# 05-AD9546_StrapsXtal.net
KiCad netlist of a schematic drawn in Altium Designer
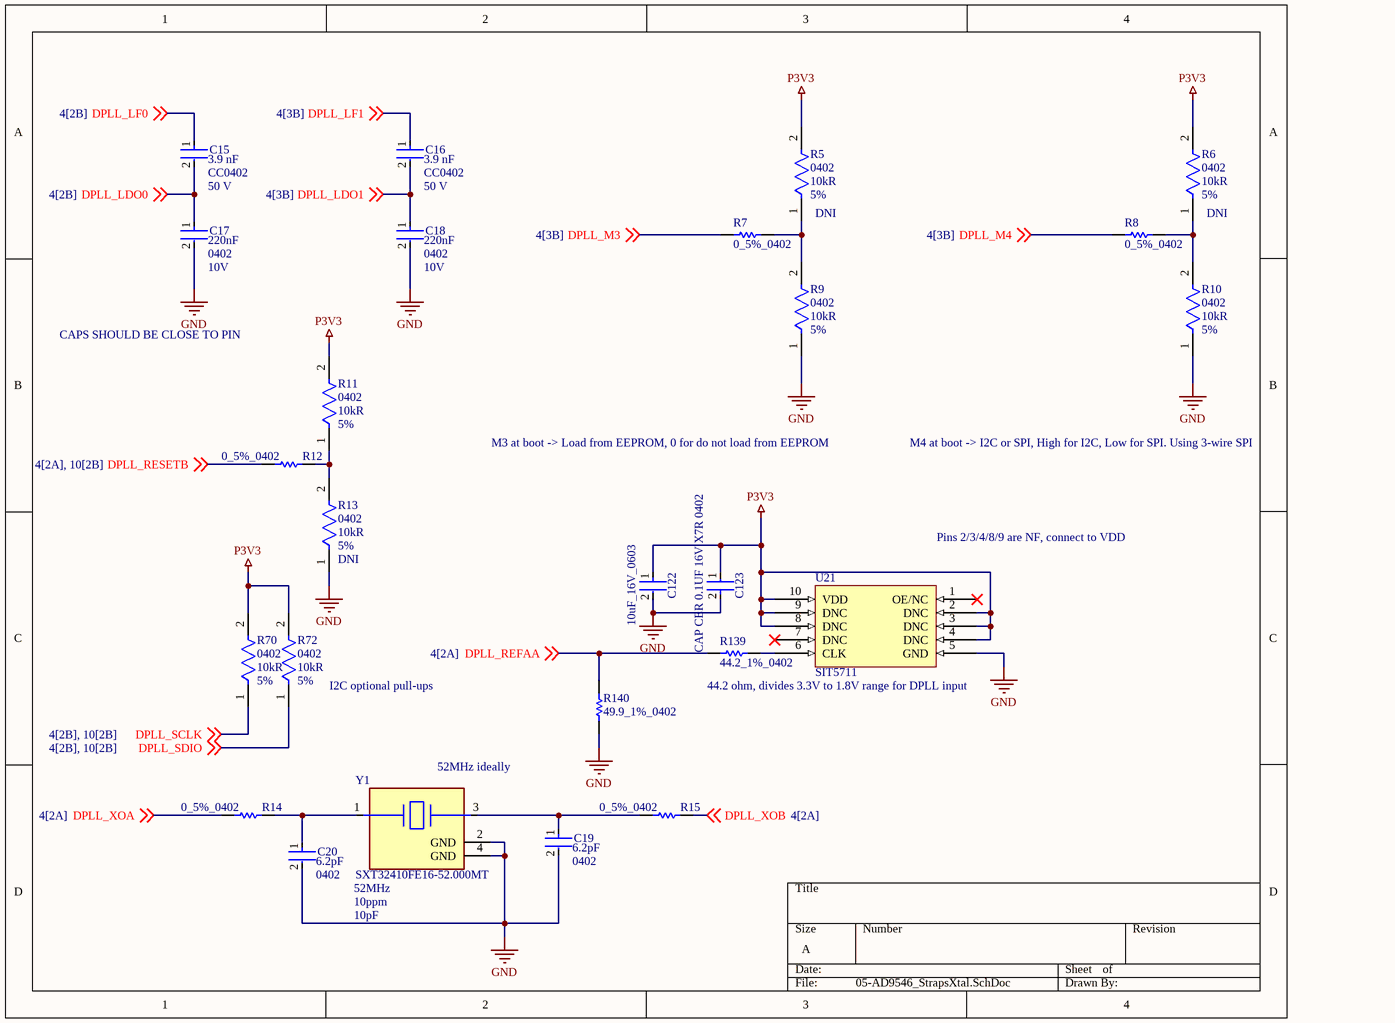
[diagram p0: 05-AD9546_StrapsXtal.SchDoc]

(export (version "E")
  (design (tool "Eeschema 10.0.6"))
  (components
    (comp (ref "C15")
      (value "3.9 nF")
      (footprint "FP-CC0402-MFG")
      (description "CAP CER 3900PF 50V X7R 0402")
      (fields
        (field (name "OCTOPART") "https://octopart.com/cc0402krx7r9bb392-yageo-9291741")
        (field (name "TOLERANCE") "0.1")
        (field (name "VOLTAGE RATING") "50 V")
        (field (name "PACKAGE") "CC0402")
      )
      (libsource (lib "Altium Content Vault") (part "11868f565c42a9108669ba33697ecf6"))
    )
    (comp (ref "C16")
      (value "3.9 nF")
      (footprint "FP-CC0402-MFG")
      (description "CAP CER 3900PF 50V X7R 0402")
      (fields
        (field (name "OCTOPART") "https://octopart.com/cc0402krx7r9bb392-yageo-9291741")
        (field (name "TOLERANCE") "0.1")
        (field (name "VOLTAGE RATING") "50 V")
        (field (name "PACKAGE") "CC0402")
      )
      (libsource (lib "Altium Content Vault") (part "11868f565c42a9108669ba33697ecf6"))
    )
    (comp (ref "C17")
      (value "GRM155R61A224KE19D")
      (footprint "FP-GRM155-0_05-IPC_A")
      (description "CAP CER 0.22UF 10V X5R 0402")
      (fields
        (field (name "VOLTAGE") "10V")
        (field (name "TOLERANCE") "10%")
        (field (name "CASE/PACKAGE") "0402")
        (field (name "CAPACITANCE") "220nF")
      )
      (libsource (lib "Altium Content Vault") (part "02cd4be3c70576c341d710602a673aa"))
    )
    (comp (ref "C18")
      (value "GRM155R61A224KE19D")
      (footprint "FP-GRM155-0_05-IPC_A")
      (description "CAP CER 0.22UF 10V X5R 0402")
      (fields
        (field (name "VOLTAGE") "10V")
        (field (name "TOLERANCE") "10%")
        (field (name "CASE/PACKAGE") "0402")
        (field (name "CAPACITANCE") "220nF")
      )
      (libsource (lib "Altium Content Vault") (part "02cd4be3c70576c341d710602a673aa"))
    )
    (comp (ref "C19")
      (value "CL05C6R2CB5NNNC")
      (footprint "FP-CL468-IPC_C")
      (description "Cap Ceramic 6.2pF 50V C0G ±0.25pF SMD 0402 +125°C Paper T/R")
      (fields (field (name "CASE/PACKAGE") "0402") (field (name "CAPACITANCE") "6.2pF"))
      (libsource (lib "Altium Content Vault") (part "b4654b650e69147ec39a6b967a45e02"))
    )
    (comp (ref "C20")
      (value "CL05C6R2CB5NNNC")
      (footprint "FP-CL468-IPC_C")
      (description "Cap Ceramic 6.2pF 50V C0G ±0.25pF SMD 0402 +125°C Paper T/R")
      (fields (field (name "CASE/PACKAGE") "0402") (field (name "CAPACITANCE") "6.2pF"))
      (libsource (lib "Altium Content Vault") (part "b4654b650e69147ec39a6b967a45e02"))
    )
    (comp (ref "C122")
      (value "10uF_16V_0603")
      (footprint "FP-C1608-MFG")
      (description "CAP CER 10UF 16V X5R 0603")
      (fields
        (field (name "OCTOPART") "https://octopart.com/c1608x5r1c106m080ab-tdk-26013480")
        (field (name "MANUFACTURER") "TDK Corporation")
      )
      (libsource (lib "Altium Content Vault") (part "11868f565c42a9108669ba33697ecf6"))
    )
    (comp (ref "C123")
      (value "GRM155R71C104KA88D")
      (footprint "FP-GRM15-MFG")
      (description "CAP CER 0.1UF 16V X7R 0402")
      (fields
        (field (name "TOLERANCE") "10%")
        (field (name "OCTOPART") "https://octopart.com/grm155r71c104ka88d-murata-196880")
        (field (name "DIGIKEY DESCRIPTION") "CAP CER 0.1UF 16V X7R 0402")
      )
      (libsource (lib "Altium Content Vault") (part "236180d848d6139a670b325ea6854c9"))
    )
    (comp (ref "R5")
      (value "CRCW040210K0JNED")
      (footprint "FP-CRCW0402-e3-IPC_B")
      (description "RES Thick Film, 10kΩ, 5%, 0.063W, 200ppm/°C, 0402")
      (fields
        (field (name "CASE/PACKAGE") "0402")
        (field (name "RESISTANCE") "10kR")
        (field (name "TOLERANCE") "5%")
        (field (name "DNI") "DNI")
      )
      (libsource (lib "Altium Content Vault") (part "1029c3af85768c4190bb7ad29bc67b5"))
    )
    (comp (ref "R6")
      (value "CRCW040210K0JNED")
      (footprint "FP-CRCW0402-e3-IPC_B")
      (description "RES Thick Film, 10kΩ, 5%, 0.063W, 200ppm/°C, 0402")
      (fields
        (field (name "CASE/PACKAGE") "0402")
        (field (name "RESISTANCE") "10kR")
        (field (name "TOLERANCE") "5%")
        (field (name "DNI") "DNI")
      )
      (libsource (lib "Altium Content Vault") (part "1029c3af85768c4190bb7ad29bc67b5"))
    )
    (comp (ref "R7")
      (value "0_5%_0402")
      (footprint "RESC1005X40X25ML05T10")
      (fields (field (name "PART NUMBER") "CRCW04020000Z0EDHP") (field (name "MANUFACTURER") "Vishay Dale"))
      (libsource (lib "Altium Content Vault") (part "RES"))
    )
    (comp (ref "R8")
      (value "0_5%_0402")
      (footprint "RESC1005X40X25ML05T10")
      (fields (field (name "PART NUMBER") "CRCW04020000Z0EDHP") (field (name "MANUFACTURER") "Vishay Dale"))
      (libsource (lib "Altium Content Vault") (part "RES"))
    )
    (comp (ref "R9")
      (value "CRCW040210K0JNED")
      (footprint "FP-CRCW0402-e3-IPC_B")
      (description "RES Thick Film, 10kΩ, 5%, 0.063W, 200ppm/°C, 0402")
      (fields
        (field (name "CASE/PACKAGE") "0402")
        (field (name "RESISTANCE") "10kR")
        (field (name "TOLERANCE") "5%")
      )
      (libsource (lib "Altium Content Vault") (part "1029c3af85768c4190bb7ad29bc67b5"))
    )
    (comp (ref "R10")
      (value "CRCW040210K0JNED")
      (footprint "FP-CRCW0402-e3-IPC_B")
      (description "RES Thick Film, 10kΩ, 5%, 0.063W, 200ppm/°C, 0402")
      (fields
        (field (name "CASE/PACKAGE") "0402")
        (field (name "RESISTANCE") "10kR")
        (field (name "TOLERANCE") "5%")
      )
      (libsource (lib "Altium Content Vault") (part "1029c3af85768c4190bb7ad29bc67b5"))
    )
    (comp (ref "R11")
      (value "CRCW040210K0JNED")
      (footprint "FP-CRCW0402-e3-IPC_B")
      (description "RES Thick Film, 10kΩ, 5%, 0.063W, 200ppm/°C, 0402")
      (fields
        (field (name "CASE/PACKAGE") "0402")
        (field (name "RESISTANCE") "10kR")
        (field (name "TOLERANCE") "5%")
      )
      (libsource (lib "Altium Content Vault") (part "1029c3af85768c4190bb7ad29bc67b5"))
    )
    (comp (ref "R12")
      (value "0_5%_0402")
      (footprint "RESC1005X40X25LL10T10")
      (fields (field (name "MANUFACTURER") "KOA Speer") (field (name "PART NUMBER") "RK73Z1ETTP"))
      (libsource (lib "Altium Content Vault") (part "RES"))
    )
    (comp (ref "R13")
      (value "CRCW040210K0JNED")
      (footprint "FP-CRCW0402-e3-IPC_B")
      (description "RES Thick Film, 10kΩ, 5%, 0.063W, 200ppm/°C, 0402")
      (fields
        (field (name "CASE/PACKAGE") "0402")
        (field (name "RESISTANCE") "10kR")
        (field (name "TOLERANCE") "5%")
        (field (name "DNI") "DNI")
      )
      (libsource (lib "Altium Content Vault") (part "1029c3af85768c4190bb7ad29bc67b5"))
    )
    (comp (ref "R14")
      (value "0_5%_0402")
      (footprint "RESC1005X40X25LL10T10")
      (fields (field (name "MANUFACTURER") "KOA Speer") (field (name "PART NUMBER") "RK73Z1ETTP"))
      (libsource (lib "Altium Content Vault") (part "RES"))
    )
    (comp (ref "R15")
      (value "0_5%_0402")
      (footprint "RESC1005X40X25LL10T10")
      (fields (field (name "MANUFACTURER") "KOA Speer") (field (name "PART NUMBER") "RK73Z1ETTP"))
      (libsource (lib "Altium Content Vault") (part "RES"))
    )
    (comp (ref "R70")
      (value "CRCW040210K0JNED")
      (footprint "FP-CRCW0402-e3-IPC_B")
      (description "RES Thick Film, 10kΩ, 5%, 0.063W, 200ppm/°C, 0402")
      (fields
        (field (name "CASE/PACKAGE") "0402")
        (field (name "RESISTANCE") "10kR")
        (field (name "TOLERANCE") "5%")
      )
      (libsource (lib "Altium Content Vault") (part "1029c3af85768c4190bb7ad29bc67b5"))
    )
    (comp (ref "R72")
      (value "CRCW040210K0JNED")
      (footprint "FP-CRCW0402-e3-IPC_B")
      (description "RES Thick Film, 10kΩ, 5%, 0.063W, 200ppm/°C, 0402")
      (fields
        (field (name "CASE/PACKAGE") "0402")
        (field (name "RESISTANCE") "10kR")
        (field (name "TOLERANCE") "5%")
      )
      (libsource (lib "Altium Content Vault") (part "1029c3af85768c4190bb7ad29bc67b5"))
    )
    (comp (ref "R139")
      (value "44.2_1%_0402")
      (footprint "RESC0402(1005)_M")
      (description "44R2 0.063W 1% 0402 (1005 Metric)  SMD")
      (fields (field (name "TOLERANCE") "1 %") (field (name "POWER") "0.063 W"))
      (libsource (lib "Altium Content Vault") (part "RES"))
    )
    (comp (ref "R140")
      (value "49.9_1%_0402")
      (footprint "RESC1005X40X25NL05T05")
      (fields (field (name "MANUFACTURER") "Panasonic") (field (name "PART NUMBER") "ERJ-2RKF49R9X"))
      (libsource (lib "Altium Content Vault") (part "RES"))
    )
    (comp (ref "U21")
      (value "SIT5711")
      (footprint "SIT5711")
      (libsource (lib "TimeDrive_Lib") (part "SIT5711"))
    )
    (comp (ref "Y1")
      (value "SXT32410FE16-52.000MT")
      (footprint "FP-402-MFG")
      (description "CRYSTAL 32.0000MHZ 10PF SMD")
      (fields
        (field (name "FREQUENCY") "52MHz")
        (field (name "FREQUENCY STABILITY") "10ppm")
        (field (name "TOLERANCE") "10ppm")
        (field (name "LOAD CAPACITANCE") "10pF")
      )
      (libsource (lib "Altium Content Vault") (part "aa2bcc763e4d5c877d8ff97ea4c95a3"))
    )
  )
  (nets
    (net (code "1") (name "DPLL_LDO0") (class "Default")
      (node (ref "C15") (pin "2") (pinfunction "2_2") (pintype "passive"))
      (node (ref "C17") (pin "1") (pinfunction "1_1") (pintype "passive"))
    )
    (net (code "2") (name "DPLL_LDO1") (class "Default")
      (node (ref "C16") (pin "2") (pinfunction "2_2") (pintype "passive"))
      (node (ref "C18") (pin "1") (pinfunction "1_1") (pintype "passive"))
    )
    (net (code "3") (name "DPLL_LF0") (class "Default")
      (node (ref "C15") (pin "1") (pinfunction "1_1") (pintype "passive"))
    )
    (net (code "4") (name "DPLL_LF1") (class "Default")
      (node (ref "C16") (pin "1") (pinfunction "1_1") (pintype "passive"))
    )
    (net (code "5") (name "DPLL_M3") (class "Default")
      (node (ref "R7") (pin "1") (pinfunction "1_1") (pintype "passive"))
    )
    (net (code "6") (name "DPLL_M4") (class "Default")
      (node (ref "R8") (pin "1") (pinfunction "1_1") (pintype "passive"))
    )
    (net (code "7") (name "DPLL_REFAA") (class "Default")
      (node (ref "R139") (pin "1") (pinfunction "1_1") (pintype "passive"))
      (node (ref "R140") (pin "2") (pinfunction "2_2") (pintype "passive"))
    )
    (net (code "8") (name "DPLL_RESETB") (class "Default")
      (node (ref "R12") (pin "1") (pinfunction "1_1") (pintype "passive"))
    )
    (net (code "9") (name "DPLL_SCLK") (class "Default")
      (node (ref "R70") (pin "1") (pinfunction "1_1") (pintype "passive"))
    )
    (net (code "10") (name "DPLL_SDIO") (class "Default")
      (node (ref "R72") (pin "1") (pinfunction "1_1") (pintype "passive"))
    )
    (net (code "11") (name "DPLL_XOA") (class "Default")
      (node (ref "R14") (pin "1") (pinfunction "1_1") (pintype "passive"))
    )
    (net (code "12") (name "DPLL_XOB") (class "Default")
      (node (ref "R15") (pin "2") (pinfunction "2_2") (pintype "passive"))
    )
    (net (code "13") (name "GND") (class "Default")
      (node (ref "C122") (pin "2") (pinfunction "2_2") (pintype "passive"))
      (node (ref "C123") (pin "2") (pinfunction "2_2") (pintype "passive"))
      (node (ref "C17") (pin "2") (pinfunction "2_2") (pintype "passive"))
      (node (ref "C18") (pin "2") (pinfunction "2_2") (pintype "passive"))
      (node (ref "C19") (pin "2") (pinfunction "2_2") (pintype "passive"))
      (node (ref "C20") (pin "2") (pinfunction "2_2") (pintype "passive"))
      (node (ref "R10") (pin "1") (pinfunction "1_1") (pintype "passive"))
      (node (ref "R13") (pin "1") (pinfunction "1_1") (pintype "passive"))
      (node (ref "R140") (pin "1") (pinfunction "1_1") (pintype "passive"))
      (node (ref "R9") (pin "1") (pinfunction "1_1") (pintype "passive"))
      (node (ref "U21") (pin "5") (pinfunction "GND_5") (pintype "input"))
      (node (ref "Y1") (pin "2") (pinfunction "GND_2") (pintype "power_in"))
      (node (ref "Y1") (pin "4") (pinfunction "GND_4") (pintype "power_in"))
    )
    (net (code "14") (name "Net-(C19-Pad1)") (class "Default")
      (node (ref "C19") (pin "1") (pinfunction "1_1") (pintype "passive"))
      (node (ref "R15") (pin "1") (pinfunction "1_1") (pintype "passive"))
      (node (ref "Y1") (pin "3") (pinfunction "3_3") (pintype "passive"))
    )
    (net (code "15") (name "Net-(C20-Pad1)") (class "Default")
      (node (ref "C20") (pin "1") (pinfunction "1_1") (pintype "passive"))
      (node (ref "R14") (pin "2") (pinfunction "2_2") (pintype "passive"))
      (node (ref "Y1") (pin "1") (pinfunction "1_1") (pintype "passive"))
    )
    (net (code "16") (name "Net-(R5-Pad1)") (class "Default")
      (node (ref "R5") (pin "1") (pinfunction "1_1") (pintype "passive"))
      (node (ref "R7") (pin "2") (pinfunction "2_2") (pintype "passive"))
      (node (ref "R9") (pin "2") (pinfunction "2_2") (pintype "passive"))
    )
    (net (code "17") (name "Net-(R10-Pad2)") (class "Default")
      (node (ref "R10") (pin "2") (pinfunction "2_2") (pintype "passive"))
      (node (ref "R6") (pin "1") (pinfunction "1_1") (pintype "passive"))
      (node (ref "R8") (pin "2") (pinfunction "2_2") (pintype "passive"))
    )
    (net (code "18") (name "Net-(R11-Pad1)") (class "Default")
      (node (ref "R11") (pin "1") (pinfunction "1_1") (pintype "passive"))
      (node (ref "R12") (pin "2") (pinfunction "2_2") (pintype "passive"))
      (node (ref "R13") (pin "2") (pinfunction "2_2") (pintype "passive"))
    )
    (net (code "19") (name "Net-(U21-CLK)") (class "Default")
      (node (ref "R139") (pin "2") (pinfunction "2_2") (pintype "passive"))
      (node (ref "U21") (pin "6") (pinfunction "CLK_6") (pintype "input"))
    )
    (net (code "20") (name "P3V3") (class "Default")
      (node (ref "C122") (pin "1") (pinfunction "1_1") (pintype "passive"))
      (node (ref "C123") (pin "1") (pinfunction "1_1") (pintype "passive"))
      (node (ref "R11") (pin "2") (pinfunction "2_2") (pintype "passive"))
      (node (ref "R5") (pin "2") (pinfunction "2_2") (pintype "passive"))
      (node (ref "R6") (pin "2") (pinfunction "2_2") (pintype "passive"))
      (node (ref "R70") (pin "2") (pinfunction "2_2") (pintype "passive"))
      (node (ref "R72") (pin "2") (pinfunction "2_2") (pintype "passive"))
      (node (ref "U21") (pin "10") (pinfunction "VDD_10") (pintype "input"))
      (node (ref "U21") (pin "2") (pinfunction "DNC_2") (pintype "input"))
      (node (ref "U21") (pin "3") (pinfunction "DNC_3") (pintype "input"))
      (node (ref "U21") (pin "4") (pinfunction "DNC_4") (pintype "input"))
      (node (ref "U21") (pin "8") (pinfunction "DNC_8") (pintype "input"))
      (node (ref "U21") (pin "9") (pinfunction "DNC_9") (pintype "input"))
    )
    (net (code "21") (name "unconnected-(U21-DNC-Pad7)") (class "Default")
      (node (ref "U21") (pin "7") (pinfunction "DNC_7") (pintype "input+no_connect"))
    )
    (net (code "22") (name "unconnected-(U21-OE{slash}NC-Pad1)") (class "Default")
      (node (ref "U21") (pin "1") (pinfunction "OE/NC_1") (pintype "input+no_connect"))
    )
  )
)
